# TK532_Kondensatorkort.net
KiCad netlist of a schematic drawn in Altium Designer
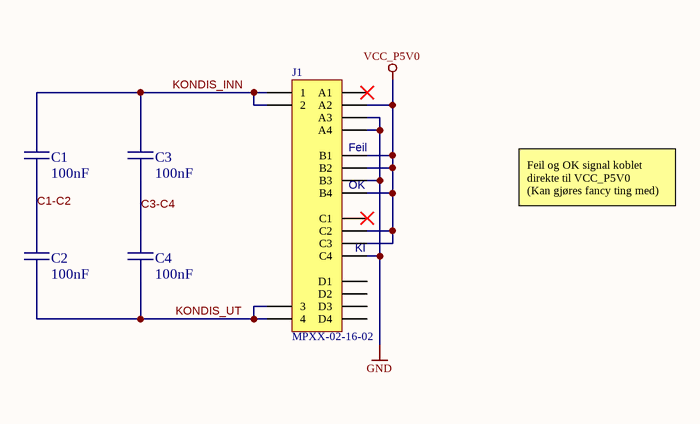
[diagram p0: TK532_Kondensatorkort.SchDoc]

(export (version "E")
  (design (tool "Eeschema 10.0.6"))
  (components
    (comp (ref "C1")
      (value "100nF")
      (footprint "CAPAR11L45")
      (description "2kV(kanskje) polypropylene film capacitor, D22, L50")
      (libsource (lib "OVLib_64") (part "CAP"))
    )
    (comp (ref "C2")
      (value "100nF")
      (footprint "CAPAR11L45")
      (description "2kV(kanskje) polypropylene film capacitor, D22, L50")
      (libsource (lib "OVLib_64") (part "CAP"))
    )
    (comp (ref "C3")
      (value "100nF")
      (footprint "CAPAR11L45")
      (description "2kV(kanskje) polypropylene film capacitor, D22, L50")
      (libsource (lib "OVLib_64") (part "CAP"))
    )
    (comp (ref "C4")
      (value "100nF")
      (footprint "CAPAR11L45")
      (description "2kV(kanskje) polypropylene film capacitor, D22, L50")
      (libsource (lib "OVLib_64") (part "CAP"))
    )
    (comp (ref "J1")
      (value "MPXX-02-16-02")
      (footprint "MPTC-02-16-02-01-03-L-RA-SD")
      (description "SAMTEC Connector")
      (libsource (lib "OVLib_64") (part "MPXX-02-16-02"))
    )
  )
  (nets
    (net (code "1") (name "/C1-C2") (class "Default")
      (node (ref "C1") (pin "1") (pinfunction "1_1") (pintype "passive"))
      (node (ref "C2") (pin "2") (pinfunction "2_2") (pintype "passive"))
    )
    (net (code "2") (name "/C3-C4") (class "Default")
      (node (ref "C3") (pin "1") (pinfunction "1_1") (pintype "passive"))
      (node (ref "C4") (pin "2") (pinfunction "2_2") (pintype "passive"))
    )
    (net (code "3") (name "/KONDIS_INN") (class "Default")
      (node (ref "C1") (pin "2") (pinfunction "2_2") (pintype "passive"))
      (node (ref "C3") (pin "2") (pinfunction "2_2") (pintype "passive"))
      (node (ref "J1") (pin "1") (pinfunction "1_1") (pintype "passive"))
      (node (ref "J1") (pin "2") (pinfunction "2_2") (pintype "passive"))
    )
    (net (code "4") (name "/KONDIS_UT") (class "Default")
      (node (ref "C2") (pin "1") (pinfunction "1_1") (pintype "passive"))
      (node (ref "C4") (pin "1") (pinfunction "1_1") (pintype "passive"))
      (node (ref "J1") (pin "3") (pinfunction "3_3") (pintype "passive"))
      (node (ref "J1") (pin "4") (pinfunction "4_4") (pintype "passive"))
    )
    (net (code "5") (name "GND") (class "Default")
      (node (ref "J1") (pin "11") (pinfunction "B3_11") (pintype "passive"))
      (node (ref "J1") (pin "16") (pinfunction "C4_16") (pintype "passive"))
      (node (ref "J1") (pin "7") (pinfunction "A3_7") (pintype "passive"))
      (node (ref "J1") (pin "8") (pinfunction "A4_8") (pintype "passive"))
    )
    (net (code "6") (name "VCC_P5V0") (class "Default")
      (node (ref "J1") (pin "10") (pinfunction "B2_10") (pintype "passive"))
      (node (ref "J1") (pin "12") (pinfunction "B4_12") (pintype "passive"))
      (node (ref "J1") (pin "14") (pinfunction "C2_14") (pintype "passive"))
      (node (ref "J1") (pin "15") (pinfunction "C3_15") (pintype "passive"))
      (node (ref "J1") (pin "6") (pinfunction "A2_6") (pintype "passive"))
      (node (ref "J1") (pin "9") (pinfunction "B1_9") (pintype "passive"))
    )
    (net (code "7") (name "unconnected-(J1-A1-Pad5)") (class "Default")
      (node (ref "J1") (pin "5") (pinfunction "A1_5") (pintype "passive+no_connect"))
    )
    (net (code "8") (name "unconnected-(J1-C1-Pad13)") (class "Default")
      (node (ref "J1") (pin "13") (pinfunction "C1_13") (pintype "passive+no_connect"))
    )
    (net (code "9") (name "unconnected-(J1-D1-Pad17)") (class "Default")
      (node (ref "J1") (pin "17") (pinfunction "D1_17") (pintype "passive"))
    )
    (net (code "10") (name "unconnected-(J1-D2-Pad18)") (class "Default")
      (node (ref "J1") (pin "18") (pinfunction "D2_18") (pintype "passive"))
    )
    (net (code "11") (name "unconnected-(J1-D3-Pad19)") (class "Default")
      (node (ref "J1") (pin "19") (pinfunction "D3_19") (pintype "passive"))
    )
    (net (code "12") (name "unconnected-(J1-D4-Pad20)") (class "Default")
      (node (ref "J1") (pin "20") (pinfunction "D4_20") (pintype "passive"))
    )
  )
)
